# imu.net
KiCad netlist of a schematic drawn in Altium Designer
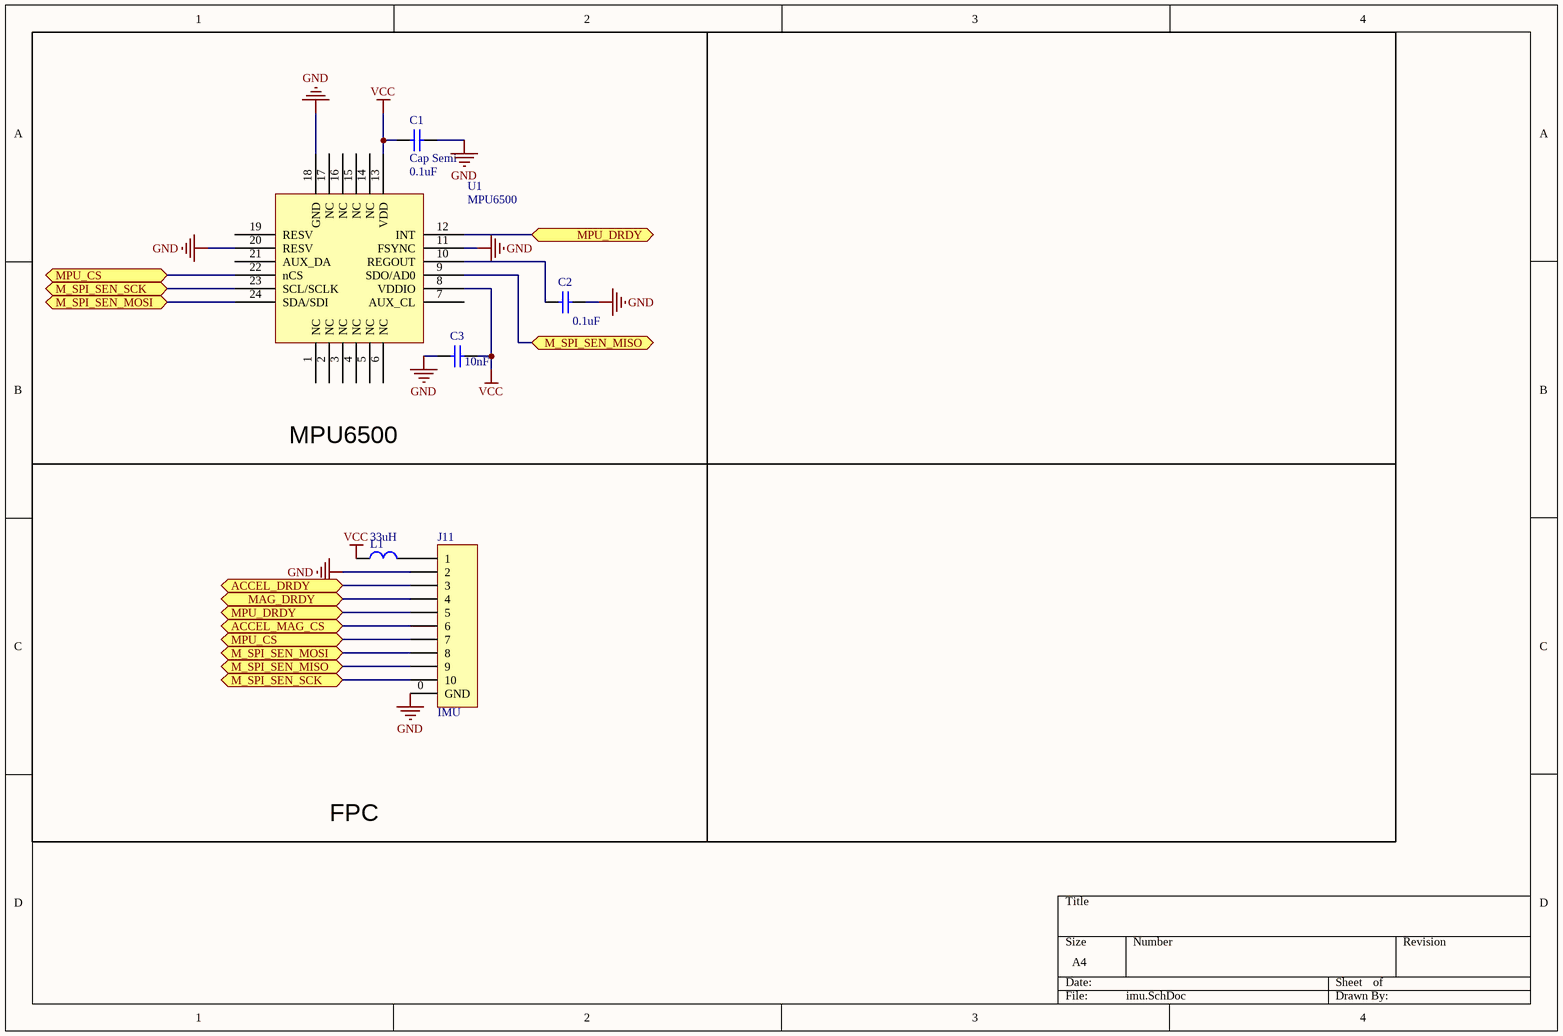
[diagram p0: imu.SchDoc]

(export (version "E")
  (design (tool "Eeschema 10.0.6"))
  (components
    (comp (ref "C1")
      (value "Cap Semi")
      (footprint "1608[0603]")
      (description "Capacitor (Semiconductor SIM Model)")
      (fields (field (name "ALTIUM_VALUE") "0.1uF") (field (name "PUBLISHER") "Altium Limited"))
      (libsource (lib "Miscellaneous Devices") (part "Cap Semi"))
    )
    (comp (ref "C2")
      (value "0.1uF")
      (footprint "1608[0603]")
      (description "Capacitor (Semiconductor SIM Model)")
      (fields (field (name "Comment") "Cap Semi") (field (name "PUBLISHER") "Altium Limited"))
      (libsource (lib "Miscellaneous Devices") (part "Cap Semi"))
    )
    (comp (ref "C3")
      (value "10nF")
      (footprint "1608[0603]")
      (description "Capacitor (Semiconductor SIM Model)")
      (fields (field (name "Comment") "Cap Semi") (field (name "PUBLISHER") "Altium Limited"))
      (libsource (lib "Miscellaneous Devices") (part "Cap Semi"))
    )
    (comp (ref "J11")
      (value "IMU")
      (footprint "fpc_10Pin")
      (description "Header, 8-Pin")
      (fields (field (name "PUBLISHER") "Altium Limited"))
      (libsource (lib "Zzhsch") (part "DF13_10"))
    )
    (comp (ref "L1")
      (value "33uH")
      (footprint "J1-0603")
      (description "Inductor")
      (fields (field (name "PUBLISHER") "Altium Limited"))
      (libsource (lib "Zzhsch") (part "Inductor_smt"))
    )
    (comp (ref "U1")
      (value "MPU6500")
      (footprint "QFN40-MPU6500")
      (libsource (lib "MPU6500") (part "Component_1"))
    )
  )
  (nets
    (net (code "1") (name "/ACCEL_DRDY") (class "Default")
      (node (ref "J11") (pin "3") (pinfunction "3_3") (pintype "passive"))
    )
    (net (code "2") (name "/ACCEL_MAG_CS") (class "Default")
      (node (ref "J11") (pin "6") (pinfunction "6_6") (pintype "passive"))
    )
    (net (code "3") (name "/MAG_DRDY") (class "Default")
      (node (ref "J11") (pin "4") (pinfunction "4_4") (pintype "passive"))
    )
    (net (code "4") (name "/MPU_CS") (class "Default")
      (node (ref "J11") (pin "7") (pinfunction "7_7") (pintype "passive"))
      (node (ref "U1") (pin "22") (pinfunction "nCS_22") (pintype "passive"))
    )
    (net (code "5") (name "/MPU_DRDY") (class "Default")
      (node (ref "J11") (pin "5") (pinfunction "5_5") (pintype "passive"))
      (node (ref "U1") (pin "12") (pinfunction "INT_12") (pintype "passive"))
    )
    (net (code "6") (name "/M_SPI_SEN_MISO") (class "Default")
      (node (ref "J11") (pin "9") (pinfunction "9_9") (pintype "passive"))
      (node (ref "U1") (pin "9") (pinfunction "SDO/AD0_9") (pintype "passive"))
    )
    (net (code "7") (name "/M_SPI_SEN_MOSI") (class "Default")
      (node (ref "J11") (pin "8") (pinfunction "8_8") (pintype "passive"))
      (node (ref "U1") (pin "24") (pinfunction "SDA/SDI_24") (pintype "passive"))
    )
    (net (code "8") (name "/M_SPI_SEN_SCK") (class "Default")
      (node (ref "J11") (pin "10") (pinfunction "10_10") (pintype "passive"))
      (node (ref "U1") (pin "23") (pinfunction "SCL/SCLK_23") (pintype "passive"))
    )
    (net (code "9") (name "GND") (class "Default")
      (node (ref "C1") (pin "1") (pinfunction "1_1") (pintype "passive"))
      (node (ref "C2") (pin "1") (pinfunction "1_1") (pintype "passive"))
      (node (ref "C3") (pin "2") (pinfunction "2_2") (pintype "passive"))
      (node (ref "J11") (pin "0") (pinfunction "GND_0") (pintype "passive"))
      (node (ref "J11") (pin "2") (pinfunction "2_2") (pintype "passive"))
      (node (ref "U1") (pin "11") (pinfunction "FSYNC_11") (pintype "passive"))
      (node (ref "U1") (pin "18") (pinfunction "GND_18") (pintype "passive"))
      (node (ref "U1") (pin "20") (pinfunction "RESV_20") (pintype "passive"))
    )
    (net (code "10") (name "Net-(J11-Pad1)") (class "Default")
      (node (ref "J11") (pin "1") (pinfunction "1_1") (pintype "passive"))
      (node (ref "L1") (pin "2") (pinfunction "2_2") (pintype "passive"))
    )
    (net (code "11") (name "Net-(U1-REGOUT)") (class "Default")
      (node (ref "C2") (pin "2") (pinfunction "2_2") (pintype "passive"))
      (node (ref "U1") (pin "10") (pinfunction "REGOUT_10") (pintype "passive"))
    )
    (net (code "12") (name "VCC") (class "Default")
      (node (ref "C1") (pin "2") (pinfunction "2_2") (pintype "passive"))
      (node (ref "C3") (pin "1") (pinfunction "1_1") (pintype "passive"))
      (node (ref "L1") (pin "1") (pinfunction "1_1") (pintype "passive"))
      (node (ref "U1") (pin "13") (pinfunction "VDD_13") (pintype "passive"))
      (node (ref "U1") (pin "8") (pinfunction "VDDIO_8") (pintype "passive"))
    )
    (net (code "13") (name "unconnected-(U1-AUX_CL-Pad7)") (class "Default")
      (node (ref "U1") (pin "7") (pinfunction "AUX_CL_7") (pintype "passive"))
    )
    (net (code "14") (name "unconnected-(U1-AUX_DA-Pad21)") (class "Default")
      (node (ref "U1") (pin "21") (pinfunction "AUX_DA_21") (pintype "passive"))
    )
    (net (code "15") (name "unconnected-(U1-NC-Pad1)") (class "Default")
      (node (ref "U1") (pin "1") (pinfunction "NC_1") (pintype "passive"))
    )
    (net (code "16") (name "unconnected-(U1-NC-Pad2)") (class "Default")
      (node (ref "U1") (pin "2") (pinfunction "NC_2") (pintype "passive"))
    )
    (net (code "17") (name "unconnected-(U1-NC-Pad3)") (class "Default")
      (node (ref "U1") (pin "3") (pinfunction "NC_3") (pintype "passive"))
    )
    (net (code "18") (name "unconnected-(U1-NC-Pad4)") (class "Default")
      (node (ref "U1") (pin "4") (pinfunction "NC_4") (pintype "passive"))
    )
    (net (code "19") (name "unconnected-(U1-NC-Pad5)") (class "Default")
      (node (ref "U1") (pin "5") (pinfunction "NC_5") (pintype "passive"))
    )
    (net (code "20") (name "unconnected-(U1-NC-Pad6)") (class "Default")
      (node (ref "U1") (pin "6") (pinfunction "NC_6") (pintype "passive"))
    )
    (net (code "21") (name "unconnected-(U1-NC-Pad14)") (class "Default")
      (node (ref "U1") (pin "14") (pinfunction "NC_14") (pintype "passive"))
    )
    (net (code "22") (name "unconnected-(U1-NC-Pad15)") (class "Default")
      (node (ref "U1") (pin "15") (pinfunction "NC_15") (pintype "passive"))
    )
    (net (code "23") (name "unconnected-(U1-NC-Pad16)") (class "Default")
      (node (ref "U1") (pin "16") (pinfunction "NC_16") (pintype "passive"))
    )
    (net (code "24") (name "unconnected-(U1-NC-Pad17)") (class "Default")
      (node (ref "U1") (pin "17") (pinfunction "NC_17") (pintype "passive"))
    )
    (net (code "25") (name "unconnected-(U1-RESV-Pad19)") (class "Default")
      (node (ref "U1") (pin "19") (pinfunction "RESV_19") (pintype "passive"))
    )
  )
)
